# temperature-controller.net
KiCad netlist of a schematic drawn in Altium Designer
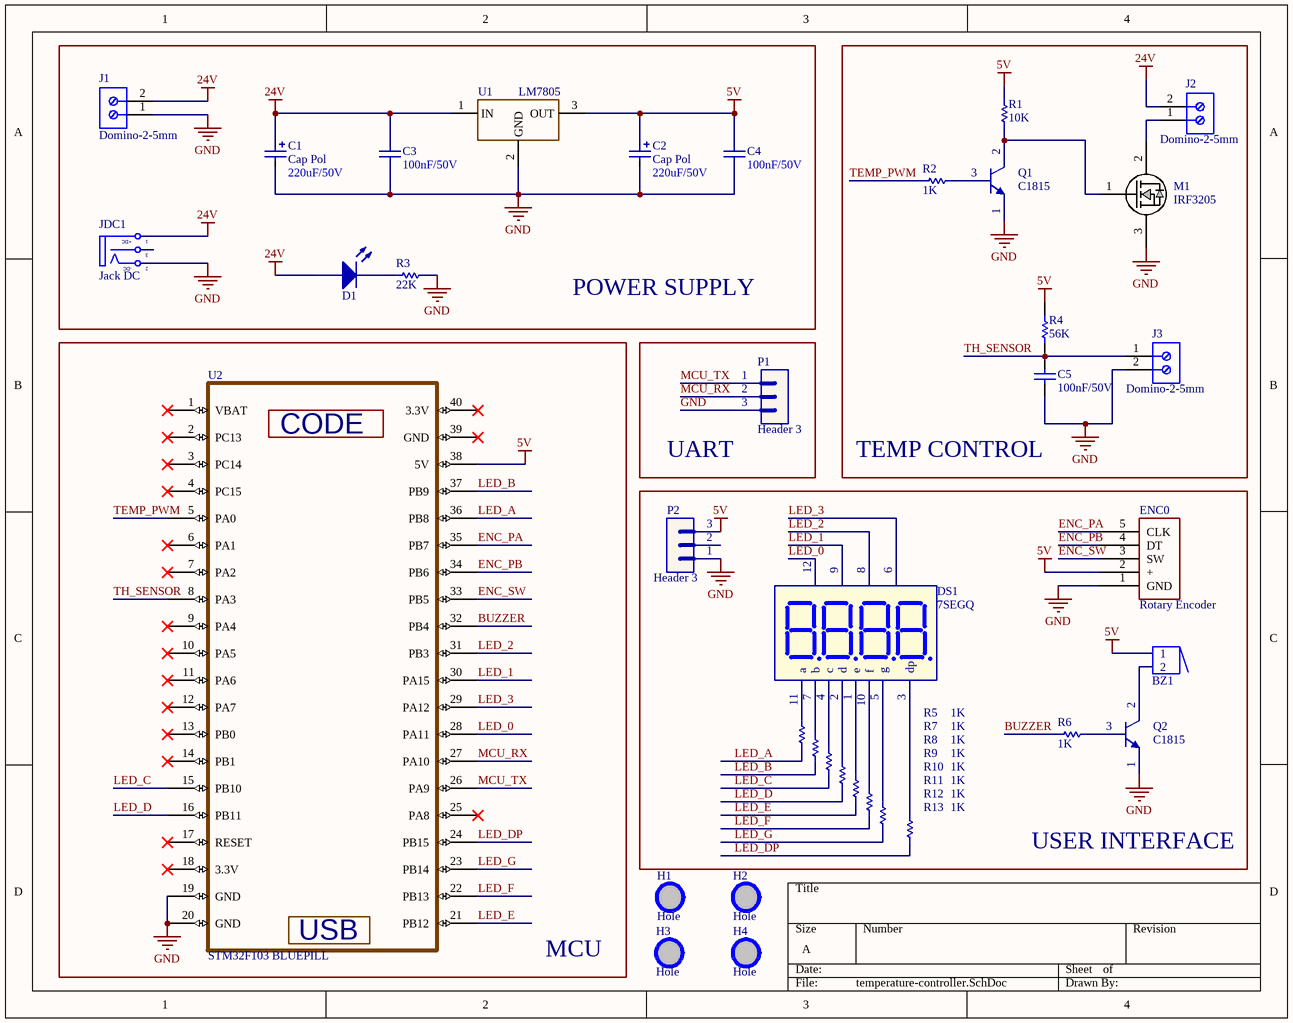
[diagram p0: temperature-controller.SchDoc]

(export (version "E")
  (design (tool "Eeschema 10.0.6"))
  (components
    (comp (ref "BZ1")
      (value "Buzzer")
      (footprint "BUZZER")
      (libsource (lib "temperature-controller-lib") (part "Buzzer"))
    )
    (comp (ref "C1")
      (value "Cap Pol")
      (footprint "CP1.5/2.5")
      (description "Polarized Capacitor (Radial)")
      (fields (field (name "ALTIUM_VALUE") "220uF/50V"))
      (libsource (lib "Capacitor-TH") (part "Cap-TH-Pol"))
    )
    (comp (ref "C2")
      (value "Cap Pol")
      (footprint "CP1.5/2.5")
      (description "Polarized Capacitor (Radial)")
      (fields (field (name "ALTIUM_VALUE") "220uF/50V"))
      (libsource (lib "Capacitor-TH") (part "Cap-TH-Pol"))
    )
    (comp (ref "C3")
      (value "100nF/50V")
      (footprint "CN1")
      (description "Capacitor")
      (fields (field (name "Comment") "Cap Non-Pol"))
      (libsource (lib "Capacitor-TH") (part "Cap-TH-NonPol"))
    )
    (comp (ref "C4")
      (value "100nF/50V")
      (footprint "CN1")
      (description "Capacitor")
      (fields (field (name "Comment") "Cap Non-Pol"))
      (libsource (lib "Capacitor-TH") (part "Cap-TH-NonPol"))
    )
    (comp (ref "C5")
      (value "100nF/50V")
      (footprint "CAP-SM-0805")
      (description "CAP CER 0.1UF 50V Y5V 0805")
      (fields
        (field (name "MANUFACTURER") "Samsung Electro-Mechanics")
        (field (name "MANUFACTURER PART NUMBER") "CL21F104ZBCNNNC")
      )
      (libsource (lib "Capacitor") (part "Cap-100nF-50V-0805"))
    )
    (comp (ref "D1") (value "LED") (footprint "LED-3mm") (libsource (lib "LED-TH") (part "LED")))
    (comp (ref "DS1")
      (value "7SEGQ")
      (footprint "7SEGQ")
      (description "Four 7 Seg Dipslay")
      (libsource (lib "LED-TH") (part "LED7Q"))
    )
    (comp (ref "ENC0")
      (value "Rotary Encoder")
      (footprint "Rotary-Encoder")
      (libsource (lib "temperature-controller-lib") (part "Rotary Encoder"))
    )
    (comp (ref "H1")
      (value "Hole")
      (footprint "HOLE-3mm")
      (description "Hole 3mm")
      (libsource (lib "temperature-controller-lib") (part "Hole"))
    )
    (comp (ref "H2")
      (value "Hole")
      (footprint "HOLE-3mm")
      (description "Hole 3mm")
      (libsource (lib "temperature-controller-lib") (part "Hole"))
    )
    (comp (ref "H3")
      (value "Hole")
      (footprint "HOLE-3mm")
      (description "Hole 3mm")
      (libsource (lib "temperature-controller-lib") (part "Hole"))
    )
    (comp (ref "H4")
      (value "Hole")
      (footprint "HOLE-3mm")
      (description "Hole 3mm")
      (libsource (lib "temperature-controller-lib") (part "Hole"))
    )
    (comp (ref "J1")
      (value "Domino-2-5mm")
      (footprint "DOMINO-2-5MM")
      (description "WR-TBL Serie 1347 Horizontal Cable Entry, Pressure Clamp, pitch 5mm, 2p")
      (fields (field (name "PART NUMBER") "691134710002") (field (name "PUBLISHER") "Wurth Elektronik"))
      (libsource (lib "Header-connector") (part "Domino-2-5mm"))
    )
    (comp (ref "J2")
      (value "Domino-2-5mm")
      (footprint "DOMINO-2-5MM")
      (description "WR-TBL Serie 1347 Horizontal Cable Entry, Pressure Clamp, pitch 5mm, 2p")
      (fields (field (name "PART NUMBER") "691134710002") (field (name "PUBLISHER") "Wurth Elektronik"))
      (libsource (lib "") (part "Domino-2-5mm_1"))
    )
    (comp (ref "J3")
      (value "Domino-2-5mm")
      (footprint "DOMINO-2-5MM")
      (description "WR-TBL Serie 1347 Horizontal Cable Entry, Pressure Clamp, pitch 5mm, 2p")
      (fields (field (name "PART NUMBER") "691134710002") (field (name "PUBLISHER") "Wurth Elektronik"))
      (libsource (lib "Header-connector") (part "Domino-2-5mm"))
    )
    (comp (ref "JDC1")
      (value "Jack DC")
      (footprint "JACK-DC")
      (description "Jack DC input")
      (libsource (lib "Header-connector") (part "Jack DC"))
    )
    (comp (ref "M1")
      (value "IRF3205")
      (footprint "TO220AB")
      (description "N-Channel 55V 110A (Tc) 200W (Tc) Through Hole TO-220AB")
      (libsource (lib "MOSFET-TH") (part "IRF3205"))
    )
    (comp (ref "P1")
      (value "Header 3")
      (footprint "JP3")
      (description "Header, 3-Pin")
      (fields (field (name "PUBLISHER") "Altium Limited"))
      (libsource (lib "") (part "Header 3_1"))
    )
    (comp (ref "P2")
      (value "Header 3")
      (footprint "JP3")
      (description "Header, 3-Pin")
      (fields (field (name "PUBLISHER") "Altium Limited"))
      (libsource (lib "Header-connector") (part "Header 3"))
    )
    (comp (ref "Q1") (value "C1815") (footprint "QTO-92") (libsource (lib "BJT") (part "C1815")))
    (comp (ref "Q2") (value "C1815") (footprint "QTO-92") (libsource (lib "BJT") (part "C1815")))
    (comp (ref "R1")
      (value "10K")
      (footprint "RES 1/4W")
      (fields (field (name "Comment") "Resistor 1/4W"))
      (libsource (lib "Resistor-TH") (part "Res"))
    )
    (comp (ref "R2")
      (value "1K")
      (footprint "RES 1/4W")
      (fields (field (name "Comment") "Resistor 1/4W"))
      (libsource (lib "Resistor-TH") (part "Res"))
    )
    (comp (ref "R3")
      (value "22K")
      (footprint "RES 1/4W")
      (fields (field (name "Comment") "Resistor 1/4W"))
      (libsource (lib "Resistor-TH") (part "Res"))
    )
    (comp (ref "R4")
      (value "56K")
      (footprint "Resistor:RES-SM-0805")
      (description "RES SMD 4.7K OHM 5% 1/8W 0805")
      (fields
        (field (name "MANUFACTURER") "Yageo")
        (field (name "MANUFACTURER PART NUMBER") "RC0805JR-074K7L")
      )
      (libsource (lib "Resistor") (part "Res-4.7K-0805"))
    )
    (comp (ref "R5")
      (value "1K")
      (footprint "RES 1/4W")
      (fields (field (name "Comment") "Resistor 1/4W"))
      (libsource (lib "Resistor-TH") (part "Res"))
    )
    (comp (ref "R6")
      (value "1K")
      (footprint "RES 1/4W")
      (fields (field (name "Comment") "Resistor 1/4W"))
      (libsource (lib "Resistor-TH") (part "Res"))
    )
    (comp (ref "R7")
      (value "1K")
      (footprint "RES 1/4W")
      (fields (field (name "Comment") "Resistor 1/4W"))
      (libsource (lib "*") (part "RES"))
    )
    (comp (ref "R8")
      (value "1K")
      (footprint "RES 1/4W")
      (fields (field (name "Comment") "Resistor 1/4W"))
      (libsource (lib "*") (part "RES"))
    )
    (comp (ref "R9")
      (value "1K")
      (footprint "RES 1/4W")
      (fields (field (name "Comment") "Resistor 1/4W"))
      (libsource (lib "*") (part "RES"))
    )
    (comp (ref "R10")
      (value "1K")
      (footprint "RES 1/4W")
      (fields (field (name "Comment") "Resistor 1/4W"))
      (libsource (lib "*") (part "RES"))
    )
    (comp (ref "R11")
      (value "1K")
      (footprint "RES 1/4W")
      (fields (field (name "Comment") "Resistor 1/4W"))
      (libsource (lib "*") (part "RES"))
    )
    (comp (ref "R12")
      (value "1K")
      (footprint "RES 1/4W")
      (fields (field (name "Comment") "Resistor 1/4W"))
      (libsource (lib "*") (part "RES"))
    )
    (comp (ref "R13")
      (value "1K")
      (footprint "RES 1/4W")
      (fields (field (name "Comment") "Resistor 1/4W"))
      (libsource (lib "*") (part "RES"))
    )
    (comp (ref "U1")
      (value "LM7805")
      (footprint "QTO-220")
      (description "Positive Voltage Regulator")
      (libsource (lib "temperature-controller-lib") (part "LM7805"))
    )
    (comp (ref "U2")
      (value "STM32F103 BLUEPILL")
      (footprint "STM32F103 Bluepill")
      (libsource (lib "temperature-controller-lib") (part "STM32F103 BLUEPILL"))
    )
  )
  (nets
    (net (code "1") (name "/BUZZER") (class "Default")
      (node (ref "R6") (pin "1") (pintype "passive"))
      (node (ref "U2") (pin "32") (pinfunction "PB4_32") (pintype "bidirectional"))
    )
    (net (code "2") (name "/ENC_PA") (class "Default")
      (node (ref "ENC0") (pin "5") (pinfunction "CLK_5") (pintype "passive"))
      (node (ref "U2") (pin "35") (pinfunction "PB7_35") (pintype "bidirectional"))
    )
    (net (code "3") (name "/ENC_PB") (class "Default")
      (node (ref "ENC0") (pin "4") (pinfunction "DT_4") (pintype "passive"))
      (node (ref "U2") (pin "34") (pinfunction "PB6_34") (pintype "bidirectional"))
    )
    (net (code "4") (name "/ENC_SW") (class "Default")
      (node (ref "ENC0") (pin "3") (pinfunction "SW_3") (pintype "passive"))
      (node (ref "U2") (pin "33") (pinfunction "PB5_33") (pintype "bidirectional"))
    )
    (net (code "5") (name "/LED_0") (class "Default")
      (node (ref "DS1") (pin "12") (pinfunction "V1_12") (pintype "passive"))
      (node (ref "U2") (pin "28") (pinfunction "PA11_28") (pintype "bidirectional"))
    )
    (net (code "6") (name "/LED_1") (class "Default")
      (node (ref "DS1") (pin "9") (pinfunction "V2_9") (pintype "passive"))
      (node (ref "U2") (pin "30") (pinfunction "PA15_30") (pintype "bidirectional"))
    )
    (net (code "7") (name "/LED_2") (class "Default")
      (node (ref "DS1") (pin "8") (pinfunction "V3_8") (pintype "passive"))
      (node (ref "U2") (pin "31") (pinfunction "PB3_31") (pintype "bidirectional"))
    )
    (net (code "8") (name "/LED_3") (class "Default")
      (node (ref "DS1") (pin "6") (pinfunction "V4_6") (pintype "passive"))
      (node (ref "U2") (pin "29") (pinfunction "PA12_29") (pintype "bidirectional"))
    )
    (net (code "9") (name "/LED_A") (class "Default")
      (node (ref "R5") (pin "1") (pintype "passive"))
      (node (ref "U2") (pin "36") (pinfunction "PB8_36") (pintype "bidirectional"))
    )
    (net (code "10") (name "/LED_B") (class "Default")
      (node (ref "R7") (pin "1") (pintype "passive"))
      (node (ref "U2") (pin "37") (pinfunction "PB9_37") (pintype "bidirectional"))
    )
    (net (code "11") (name "/LED_C") (class "Default")
      (node (ref "R8") (pin "1") (pintype "passive"))
      (node (ref "U2") (pin "15") (pinfunction "PB10_15") (pintype "bidirectional"))
    )
    (net (code "12") (name "/LED_D") (class "Default")
      (node (ref "R9") (pin "1") (pintype "passive"))
      (node (ref "U2") (pin "16") (pinfunction "PB11_16") (pintype "bidirectional"))
    )
    (net (code "13") (name "/LED_DP") (class "Default")
      (node (ref "R13") (pin "1") (pintype "passive"))
      (node (ref "U2") (pin "24") (pinfunction "PB15_24") (pintype "bidirectional"))
    )
    (net (code "14") (name "/LED_E") (class "Default")
      (node (ref "R10") (pin "1") (pintype "passive"))
      (node (ref "U2") (pin "21") (pinfunction "PB12_21") (pintype "bidirectional"))
    )
    (net (code "15") (name "/LED_F") (class "Default")
      (node (ref "R11") (pin "1") (pintype "passive"))
      (node (ref "U2") (pin "22") (pinfunction "PB13_22") (pintype "bidirectional"))
    )
    (net (code "16") (name "/LED_G") (class "Default")
      (node (ref "R12") (pin "1") (pintype "passive"))
      (node (ref "U2") (pin "23") (pinfunction "PB14_23") (pintype "bidirectional"))
    )
    (net (code "17") (name "/MCU_RX") (class "Default")
      (node (ref "P1") (pin "2") (pinfunction "2_2") (pintype "passive"))
      (node (ref "U2") (pin "27") (pinfunction "PA10_27") (pintype "bidirectional"))
    )
    (net (code "18") (name "/MCU_TX") (class "Default")
      (node (ref "P1") (pin "1") (pinfunction "1_1") (pintype "passive"))
      (node (ref "U2") (pin "26") (pinfunction "PA9_26") (pintype "bidirectional"))
    )
    (net (code "19") (name "/TEMP_PWM") (class "Default")
      (node (ref "R2") (pin "1") (pintype "passive"))
      (node (ref "U2") (pin "5") (pinfunction "PA0_5") (pintype "bidirectional"))
    )
    (net (code "20") (name "/TH_SENSOR") (class "Default")
      (node (ref "C5") (pin "2") (pinfunction "2_2") (pintype "passive"))
      (node (ref "J3") (pin "1") (pinfunction "1_1") (pintype "passive"))
      (node (ref "R4") (pin "1") (pinfunction "1_1") (pintype "passive"))
      (node (ref "U2") (pin "8") (pinfunction "PA3_8") (pintype "bidirectional"))
    )
    (net (code "21") (name "5V") (class "Default")
      (node (ref "BZ1") (pin "1") (pinfunction "1_1") (pintype "passive"))
      (node (ref "C2") (pin "1") (pinfunction "1_1") (pintype "passive"))
      (node (ref "C4") (pin "2") (pinfunction "2_2") (pintype "passive"))
      (node (ref "ENC0") (pin "2") (pinfunction "+_2") (pintype "passive"))
      (node (ref "P2") (pin "3") (pinfunction "3_3") (pintype "passive"))
      (node (ref "R1") (pin "2") (pintype "passive"))
      (node (ref "R4") (pin "2") (pinfunction "2_2") (pintype "passive"))
      (node (ref "U1") (pin "3") (pinfunction "OUT_3") (pintype "power_in"))
      (node (ref "U2") (pin "38") (pinfunction "5V_38") (pintype "bidirectional"))
    )
    (net (code "22") (name "24V") (class "Default")
      (node (ref "C1") (pin "1") (pinfunction "1_1") (pintype "passive"))
      (node (ref "C3") (pin "2") (pinfunction "2_2") (pintype "passive"))
      (node (ref "D1") (pin "1") (pinfunction "A_1") (pintype "passive"))
      (node (ref "J1") (pin "2") (pinfunction "2_2") (pintype "passive"))
      (node (ref "J2") (pin "2") (pinfunction "2_2") (pintype "passive"))
      (node (ref "JDC1") (pin "1") (pinfunction "T_1") (pintype "passive"))
      (node (ref "U1") (pin "1") (pinfunction "IN_1") (pintype "power_in"))
    )
    (net (code "23") (name "GND") (class "Default")
      (node (ref "C1") (pin "2") (pinfunction "2_2") (pintype "passive"))
      (node (ref "C2") (pin "2") (pinfunction "2_2") (pintype "passive"))
      (node (ref "C3") (pin "1") (pinfunction "1_1") (pintype "passive"))
      (node (ref "C4") (pin "1") (pinfunction "1_1") (pintype "passive"))
      (node (ref "C5") (pin "1") (pinfunction "1_1") (pintype "passive"))
      (node (ref "ENC0") (pin "1") (pinfunction "GND_1") (pintype "passive"))
      (node (ref "J1") (pin "1") (pinfunction "1_1") (pintype "passive"))
      (node (ref "J3") (pin "2") (pinfunction "2_2") (pintype "passive"))
      (node (ref "JDC1") (pin "2") (pinfunction "TN_2") (pintype "passive"))
      (node (ref "M1") (pin "3") (pinfunction "S_3") (pintype "passive"))
      (node (ref "P1") (pin "3") (pinfunction "3_3") (pintype "passive"))
      (node (ref "P2") (pin "1") (pinfunction "1_1") (pintype "passive"))
      (node (ref "Q1") (pin "1") (pinfunction "E_1") (pintype "passive"))
      (node (ref "Q2") (pin "1") (pinfunction "E_1") (pintype "passive"))
      (node (ref "R3") (pin "2") (pintype "passive"))
      (node (ref "U1") (pin "2") (pinfunction "GND_2") (pintype "power_in"))
      (node (ref "U2") (pin "19") (pinfunction "GND_19") (pintype "bidirectional"))
      (node (ref "U2") (pin "20") (pinfunction "GND_20") (pintype "bidirectional"))
    )
    (net (code "24") (name "Net-(D1-K)") (class "Default")
      (node (ref "D1") (pin "2") (pinfunction "K_2") (pintype "passive"))
      (node (ref "R3") (pin "1") (pintype "passive"))
    )
    (net (code "25") (name "Net-(DS1-a)") (class "Default")
      (node (ref "DS1") (pin "11") (pinfunction "a_11") (pintype "passive"))
      (node (ref "R5") (pin "2") (pintype "passive"))
    )
    (net (code "26") (name "Net-(DS1-b)") (class "Default")
      (node (ref "DS1") (pin "7") (pinfunction "b_7") (pintype "passive"))
      (node (ref "R7") (pin "2") (pintype "passive"))
    )
    (net (code "27") (name "Net-(DS1-c)") (class "Default")
      (node (ref "DS1") (pin "4") (pinfunction "c_4") (pintype "passive"))
      (node (ref "R8") (pin "2") (pintype "passive"))
    )
    (net (code "28") (name "Net-(DS1-d)") (class "Default")
      (node (ref "DS1") (pin "2") (pinfunction "d_2") (pintype "passive"))
      (node (ref "R9") (pin "2") (pintype "passive"))
    )
    (net (code "29") (name "Net-(DS1-dp)") (class "Default")
      (node (ref "DS1") (pin "3") (pinfunction "dp_3") (pintype "passive"))
      (node (ref "R13") (pin "2") (pintype "passive"))
    )
    (net (code "30") (name "Net-(DS1-e)") (class "Default")
      (node (ref "DS1") (pin "1") (pinfunction "e_1") (pintype "passive"))
      (node (ref "R10") (pin "2") (pintype "passive"))
    )
    (net (code "31") (name "Net-(DS1-f)") (class "Default")
      (node (ref "DS1") (pin "10") (pinfunction "f_10") (pintype "passive"))
      (node (ref "R11") (pin "2") (pintype "passive"))
    )
    (net (code "32") (name "Net-(DS1-g)") (class "Default")
      (node (ref "DS1") (pin "5") (pinfunction "g_5") (pintype "passive"))
      (node (ref "R12") (pin "2") (pintype "passive"))
    )
    (net (code "33") (name "Net-(M1-D)") (class "Default")
      (node (ref "J2") (pin "1") (pinfunction "1_1") (pintype "passive"))
      (node (ref "M1") (pin "2") (pinfunction "D_2") (pintype "passive"))
    )
    (net (code "34") (name "Net-(M1-G)") (class "Default")
      (node (ref "M1") (pin "1") (pinfunction "G_1") (pintype "passive"))
      (node (ref "Q1") (pin "2") (pinfunction "C_2") (pintype "passive"))
      (node (ref "R1") (pin "1") (pintype "passive"))
    )
    (net (code "35") (name "Net-(Q1-B)") (class "Default")
      (node (ref "Q1") (pin "3") (pinfunction "B_3") (pintype "passive"))
      (node (ref "R2") (pin "2") (pintype "passive"))
    )
    (net (code "36") (name "Net-(Q2-B)") (class "Default")
      (node (ref "Q2") (pin "3") (pinfunction "B_3") (pintype "passive"))
      (node (ref "R6") (pin "2") (pintype "passive"))
    )
    (net (code "37") (name "Net-(Q2-C)") (class "Default")
      (node (ref "BZ1") (pin "2") (pinfunction "2_2") (pintype "passive"))
      (node (ref "Q2") (pin "2") (pinfunction "C_2") (pintype "passive"))
    )
    (net (code "38") (name "unconnected-(H1-Pad1)") (class "Default")
      (node (ref "H1") (pin "1") (pinfunction "1_1") (pintype "passive"))
    )
    (net (code "39") (name "unconnected-(H2-Pad1)") (class "Default")
      (node (ref "H2") (pin "1") (pinfunction "1_1") (pintype "passive"))
    )
    (net (code "40") (name "unconnected-(H3-Pad1)") (class "Default")
      (node (ref "H3") (pin "1") (pinfunction "1_1") (pintype "passive"))
    )
    (net (code "41") (name "unconnected-(H4-Pad1)") (class "Default")
      (node (ref "H4") (pin "1") (pinfunction "1_1") (pintype "passive"))
    )
    (net (code "42") (name "unconnected-(JDC1-S-Pad3)") (class "Default")
      (node (ref "JDC1") (pin "3") (pinfunction "S_3") (pintype "power_in"))
    )
    (net (code "43") (name "unconnected-(P2-Pad2)") (class "Default")
      (node (ref "P2") (pin "2") (pinfunction "2_2") (pintype "passive"))
    )
    (net (code "44") (name "unconnected-(U2-3.3V-Pad18)") (class "Default")
      (node (ref "U2") (pin "18") (pinfunction "3.3V_18") (pintype "bidirectional+no_connect"))
    )
    (net (code "45") (name "unconnected-(U2-3.3V-Pad40)") (class "Default")
      (node (ref "U2") (pin "40") (pinfunction "3.3V_40") (pintype "bidirectional+no_connect"))
    )
    (net (code "46") (name "unconnected-(U2-GND-Pad39)") (class "Default")
      (node (ref "U2") (pin "39") (pinfunction "GND_39") (pintype "bidirectional+no_connect"))
    )
    (net (code "47") (name "unconnected-(U2-PA1-Pad6)") (class "Default")
      (node (ref "U2") (pin "6") (pinfunction "PA1_6") (pintype "bidirectional+no_connect"))
    )
    (net (code "48") (name "unconnected-(U2-PA2-Pad7)") (class "Default")
      (node (ref "U2") (pin "7") (pinfunction "PA2_7") (pintype "bidirectional+no_connect"))
    )
    (net (code "49") (name "unconnected-(U2-PA4-Pad9)") (class "Default")
      (node (ref "U2") (pin "9") (pinfunction "PA4_9") (pintype "bidirectional+no_connect"))
    )
    (net (code "50") (name "unconnected-(U2-PA5-Pad10)") (class "Default")
      (node (ref "U2") (pin "10") (pinfunction "PA5_10") (pintype "bidirectional+no_connect"))
    )
    (net (code "51") (name "unconnected-(U2-PA6-Pad11)") (class "Default")
      (node (ref "U2") (pin "11") (pinfunction "PA6_11") (pintype "bidirectional+no_connect"))
    )
    (net (code "52") (name "unconnected-(U2-PA7-Pad12)") (class "Default")
      (node (ref "U2") (pin "12") (pinfunction "PA7_12") (pintype "bidirectional+no_connect"))
    )
    (net (code "53") (name "unconnected-(U2-PA8-Pad25)") (class "Default")
      (node (ref "U2") (pin "25") (pinfunction "PA8_25") (pintype "bidirectional+no_connect"))
    )
    (net (code "54") (name "unconnected-(U2-PB0-Pad13)") (class "Default")
      (node (ref "U2") (pin "13") (pinfunction "PB0_13") (pintype "bidirectional+no_connect"))
    )
    (net (code "55") (name "unconnected-(U2-PB1-Pad14)") (class "Default")
      (node (ref "U2") (pin "14") (pinfunction "PB1_14") (pintype "bidirectional+no_connect"))
    )
    (net (code "56") (name "unconnected-(U2-PC13-Pad2)") (class "Default")
      (node (ref "U2") (pin "2") (pinfunction "PC13_2") (pintype "bidirectional+no_connect"))
    )
    (net (code "57") (name "unconnected-(U2-PC14-Pad3)") (class "Default")
      (node (ref "U2") (pin "3") (pinfunction "PC14_3") (pintype "bidirectional+no_connect"))
    )
    (net (code "58") (name "unconnected-(U2-PC15-Pad4)") (class "Default")
      (node (ref "U2") (pin "4") (pinfunction "PC15_4") (pintype "bidirectional+no_connect"))
    )
    (net (code "59") (name "unconnected-(U2-RESET-Pad17)") (class "Default")
      (node (ref "U2") (pin "17") (pinfunction "RESET_17") (pintype "bidirectional+no_connect"))
    )
    (net (code "60") (name "unconnected-(U2-VBAT-Pad1)") (class "Default")
      (node (ref "U2") (pin "1") (pinfunction "VBAT_1") (pintype "bidirectional+no_connect"))
    )
  )
)
